# CR6.net
KiCad netlist of a schematic drawn in EAGLE
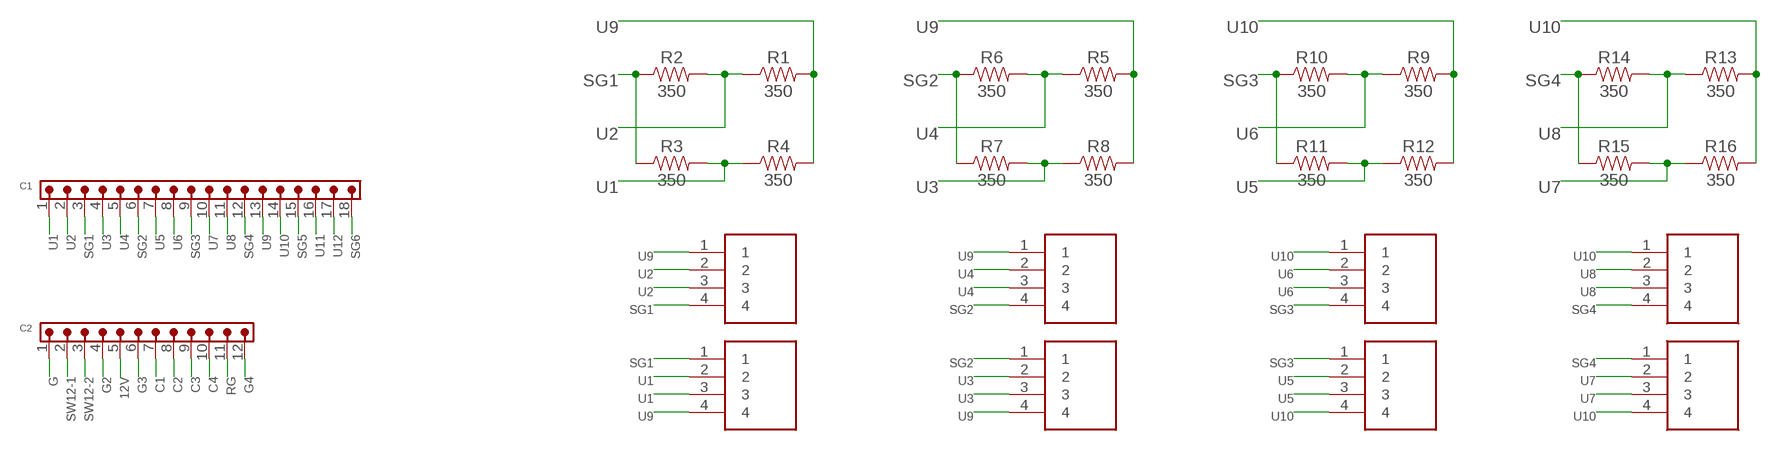
[diagram p0: schematic, sheet 1]

(export (version "E")
  (design (tool "Eeschema 10.0.6"))
  (components
    (comp (ref "C1")
      (value "WURTH_CONNECTORS_WR-TBL-PLUGGABLE-CONNECTOR_691311500018")
      (footprint "eagle-import:WURTH_CONNECTORS_WR-TBL-PLUGGABLE-CONNECTOR_691311500018")
      (libsource (lib "eagle-import") (part "WURTH_CONNECTORS_WR-TBL-PLUGGABLE-CONNECTOR_691311500018"))
    )
    (comp (ref "C2")
      (value "WURTH_CONNECTORS_WR-TBL-PLUGGABLE-CONNECTOR_691311500012")
      (footprint "eagle-import:WURTH_CONNECTORS_WR-TBL-PLUGGABLE-CONNECTOR_691311500012")
      (libsource (lib "eagle-import") (part "WURTH_CONNECTORS_WR-TBL-PLUGGABLE-CONNECTOR_691311500012"))
    )
    (comp (ref "J1")
      (value "1725672")
      (footprint "eagle-import:1725672-4-2.54")
      (fields (field (name "RS_PART_NUMBER") "3924476"))
      (libsource (lib "eagle-import") (part "1725672"))
    )
    (comp (ref "J2")
      (value "1725672")
      (footprint "eagle-import:1725672-4-2.54")
      (fields (field (name "RS_PART_NUMBER") "3924476"))
      (libsource (lib "eagle-import") (part "1725672"))
    )
    (comp (ref "J5")
      (value "1725672")
      (footprint "eagle-import:1725672-4-2.54")
      (fields (field (name "RS_PART_NUMBER") "3924476"))
      (libsource (lib "eagle-import") (part "1725672"))
    )
    (comp (ref "J6")
      (value "1725672")
      (footprint "eagle-import:1725672-4-2.54")
      (fields (field (name "RS_PART_NUMBER") "3924476"))
      (libsource (lib "eagle-import") (part "1725672"))
    )
    (comp (ref "J9")
      (value "1725672")
      (footprint "eagle-import:1725672-4-2.54")
      (fields (field (name "RS_PART_NUMBER") "3924476"))
      (libsource (lib "eagle-import") (part "1725672"))
    )
    (comp (ref "J10")
      (value "1725672")
      (footprint "eagle-import:1725672-4-2.54")
      (fields (field (name "RS_PART_NUMBER") "3924476"))
      (libsource (lib "eagle-import") (part "1725672"))
    )
    (comp (ref "J13")
      (value "1725672")
      (footprint "eagle-import:1725672-4-2.54")
      (fields (field (name "RS_PART_NUMBER") "3924476"))
      (libsource (lib "eagle-import") (part "1725672"))
    )
    (comp (ref "J14")
      (value "1725672")
      (footprint "eagle-import:1725672-4-2.54")
      (fields (field (name "RS_PART_NUMBER") "3924476"))
      (libsource (lib "eagle-import") (part "1725672"))
    )
    (comp (ref "R1")
      (value "350")
      (footprint "eagle-import:AXIAL-0.3")
      (libsource (lib "eagle-import") (part "330OHM-HORIZ-1/10W-5%"))
    )
    (comp (ref "R2")
      (value "350")
      (footprint "eagle-import:AXIAL-0.3")
      (libsource (lib "eagle-import") (part "330OHM-HORIZ-1/10W-5%"))
    )
    (comp (ref "R3")
      (value "350")
      (footprint "eagle-import:AXIAL-0.3")
      (libsource (lib "eagle-import") (part "330OHM-HORIZ-1/10W-5%"))
    )
    (comp (ref "R4")
      (value "350")
      (footprint "eagle-import:AXIAL-0.3")
      (libsource (lib "eagle-import") (part "330OHM-HORIZ-1/10W-5%"))
    )
    (comp (ref "R5")
      (value "350")
      (footprint "eagle-import:AXIAL-0.3")
      (libsource (lib "eagle-import") (part "330OHM-HORIZ-1/10W-5%"))
    )
    (comp (ref "R6")
      (value "350")
      (footprint "eagle-import:AXIAL-0.3")
      (libsource (lib "eagle-import") (part "330OHM-HORIZ-1/10W-5%"))
    )
    (comp (ref "R7")
      (value "350")
      (footprint "eagle-import:AXIAL-0.3")
      (libsource (lib "eagle-import") (part "330OHM-HORIZ-1/10W-5%"))
    )
    (comp (ref "R8")
      (value "350")
      (footprint "eagle-import:AXIAL-0.3")
      (libsource (lib "eagle-import") (part "330OHM-HORIZ-1/10W-5%"))
    )
    (comp (ref "R9")
      (value "350")
      (footprint "eagle-import:AXIAL-0.3")
      (libsource (lib "eagle-import") (part "330OHM-HORIZ-1/10W-5%"))
    )
    (comp (ref "R10")
      (value "350")
      (footprint "eagle-import:AXIAL-0.3")
      (libsource (lib "eagle-import") (part "330OHM-HORIZ-1/10W-5%"))
    )
    (comp (ref "R11")
      (value "350")
      (footprint "eagle-import:AXIAL-0.3")
      (libsource (lib "eagle-import") (part "330OHM-HORIZ-1/10W-5%"))
    )
    (comp (ref "R12")
      (value "350")
      (footprint "eagle-import:AXIAL-0.3")
      (libsource (lib "eagle-import") (part "330OHM-HORIZ-1/10W-5%"))
    )
    (comp (ref "R13")
      (value "350")
      (footprint "eagle-import:AXIAL-0.3")
      (libsource (lib "eagle-import") (part "330OHM-HORIZ-1/10W-5%"))
    )
    (comp (ref "R14")
      (value "350")
      (footprint "eagle-import:AXIAL-0.3")
      (libsource (lib "eagle-import") (part "330OHM-HORIZ-1/10W-5%"))
    )
    (comp (ref "R15")
      (value "350")
      (footprint "eagle-import:AXIAL-0.3")
      (libsource (lib "eagle-import") (part "330OHM-HORIZ-1/10W-5%"))
    )
    (comp (ref "R16")
      (value "350")
      (footprint "eagle-import:AXIAL-0.3")
      (libsource (lib "eagle-import") (part "330OHM-HORIZ-1/10W-5%"))
    )
  )
  (nets
    (net (code "1") (name "12V") (class "Default")
      (node (ref "C2") (pin "5") (pinfunction "5_5") (pintype "passive"))
    )
    (net (code "2") (name "C1") (class "Default")
      (node (ref "C2") (pin "7") (pinfunction "7_7") (pintype "passive"))
    )
    (net (code "3") (name "C2") (class "Default")
      (node (ref "C2") (pin "8") (pinfunction "8_8") (pintype "passive"))
    )
    (net (code "4") (name "C3") (class "Default")
      (node (ref "C2") (pin "9") (pinfunction "9_9") (pintype "passive"))
    )
    (net (code "5") (name "C4") (class "Default")
      (node (ref "C2") (pin "10") (pinfunction "10_10") (pintype "passive"))
    )
    (net (code "6") (name "G") (class "Default")
      (node (ref "C2") (pin "1") (pinfunction "1_1") (pintype "passive"))
    )
    (net (code "7") (name "G2") (class "Default")
      (node (ref "C2") (pin "4") (pinfunction "4_4") (pintype "passive"))
    )
    (net (code "8") (name "G3") (class "Default")
      (node (ref "C2") (pin "6") (pinfunction "6_6") (pintype "passive"))
    )
    (net (code "9") (name "G4") (class "Default")
      (node (ref "C2") (pin "12") (pinfunction "12_12") (pintype "passive"))
    )
    (net (code "10") (name "RG") (class "Default")
      (node (ref "C2") (pin "11") (pinfunction "11_11") (pintype "passive"))
    )
    (net (code "11") (name "SG1") (class "Default")
      (node (ref "C1") (pin "3") (pinfunction "3_3") (pintype "passive"))
      (node (ref "J1") (pin "4") (pinfunction "4_4") (pintype "bidirectional"))
      (node (ref "J2") (pin "1") (pinfunction "1_1") (pintype "bidirectional"))
      (node (ref "R2") (pin "P$1") (pinfunction "1_P$1") (pintype "passive"))
      (node (ref "R3") (pin "P$1") (pinfunction "1_P$1") (pintype "passive"))
    )
    (net (code "12") (name "SG2") (class "Default")
      (node (ref "C1") (pin "6") (pinfunction "6_6") (pintype "passive"))
      (node (ref "J5") (pin "4") (pinfunction "4_4") (pintype "bidirectional"))
      (node (ref "J6") (pin "1") (pinfunction "1_1") (pintype "bidirectional"))
      (node (ref "R6") (pin "P$1") (pinfunction "1_P$1") (pintype "passive"))
      (node (ref "R7") (pin "P$1") (pinfunction "1_P$1") (pintype "passive"))
    )
    (net (code "13") (name "SG3") (class "Default")
      (node (ref "C1") (pin "9") (pinfunction "9_9") (pintype "passive"))
      (node (ref "J10") (pin "1") (pinfunction "1_1") (pintype "bidirectional"))
      (node (ref "J9") (pin "4") (pinfunction "4_4") (pintype "bidirectional"))
      (node (ref "R10") (pin "P$1") (pinfunction "1_P$1") (pintype "passive"))
      (node (ref "R11") (pin "P$1") (pinfunction "1_P$1") (pintype "passive"))
    )
    (net (code "14") (name "SG4") (class "Default")
      (node (ref "C1") (pin "12") (pinfunction "12_12") (pintype "passive"))
      (node (ref "J13") (pin "4") (pinfunction "4_4") (pintype "bidirectional"))
      (node (ref "J14") (pin "1") (pinfunction "1_1") (pintype "bidirectional"))
      (node (ref "R14") (pin "P$1") (pinfunction "1_P$1") (pintype "passive"))
      (node (ref "R15") (pin "P$1") (pinfunction "1_P$1") (pintype "passive"))
    )
    (net (code "15") (name "SG5") (class "Default")
      (node (ref "C1") (pin "15") (pinfunction "15_15") (pintype "passive"))
    )
    (net (code "16") (name "SG6") (class "Default")
      (node (ref "C1") (pin "18") (pinfunction "18_18") (pintype "passive"))
    )
    (net (code "17") (name "SW12-1") (class "Default")
      (node (ref "C2") (pin "2") (pinfunction "2_2") (pintype "passive"))
    )
    (net (code "18") (name "SW12-2") (class "Default")
      (node (ref "C2") (pin "3") (pinfunction "3_3") (pintype "passive"))
    )
    (net (code "19") (name "U1") (class "Default")
      (node (ref "C1") (pin "1") (pinfunction "1_1") (pintype "passive"))
      (node (ref "J2") (pin "2") (pinfunction "2_2") (pintype "bidirectional"))
      (node (ref "J2") (pin "3") (pinfunction "3_3") (pintype "bidirectional"))
      (node (ref "R3") (pin "P$2") (pinfunction "2_P$2") (pintype "passive"))
      (node (ref "R4") (pin "P$1") (pinfunction "1_P$1") (pintype "passive"))
    )
    (net (code "20") (name "U2") (class "Default")
      (node (ref "C1") (pin "2") (pinfunction "2_2") (pintype "passive"))
      (node (ref "J1") (pin "2") (pinfunction "2_2") (pintype "bidirectional"))
      (node (ref "J1") (pin "3") (pinfunction "3_3") (pintype "bidirectional"))
      (node (ref "R1") (pin "P$1") (pinfunction "1_P$1") (pintype "passive"))
      (node (ref "R2") (pin "P$2") (pinfunction "2_P$2") (pintype "passive"))
    )
    (net (code "21") (name "U3") (class "Default")
      (node (ref "C1") (pin "4") (pinfunction "4_4") (pintype "passive"))
      (node (ref "J6") (pin "2") (pinfunction "2_2") (pintype "bidirectional"))
      (node (ref "J6") (pin "3") (pinfunction "3_3") (pintype "bidirectional"))
      (node (ref "R7") (pin "P$2") (pinfunction "2_P$2") (pintype "passive"))
      (node (ref "R8") (pin "P$1") (pinfunction "1_P$1") (pintype "passive"))
    )
    (net (code "22") (name "U4") (class "Default")
      (node (ref "C1") (pin "5") (pinfunction "5_5") (pintype "passive"))
      (node (ref "J5") (pin "2") (pinfunction "2_2") (pintype "bidirectional"))
      (node (ref "J5") (pin "3") (pinfunction "3_3") (pintype "bidirectional"))
      (node (ref "R5") (pin "P$1") (pinfunction "1_P$1") (pintype "passive"))
      (node (ref "R6") (pin "P$2") (pinfunction "2_P$2") (pintype "passive"))
    )
    (net (code "23") (name "U5") (class "Default")
      (node (ref "C1") (pin "7") (pinfunction "7_7") (pintype "passive"))
      (node (ref "J10") (pin "2") (pinfunction "2_2") (pintype "bidirectional"))
      (node (ref "J10") (pin "3") (pinfunction "3_3") (pintype "bidirectional"))
      (node (ref "R11") (pin "P$2") (pinfunction "2_P$2") (pintype "passive"))
      (node (ref "R12") (pin "P$1") (pinfunction "1_P$1") (pintype "passive"))
    )
    (net (code "24") (name "U6") (class "Default")
      (node (ref "C1") (pin "8") (pinfunction "8_8") (pintype "passive"))
      (node (ref "J9") (pin "2") (pinfunction "2_2") (pintype "bidirectional"))
      (node (ref "J9") (pin "3") (pinfunction "3_3") (pintype "bidirectional"))
      (node (ref "R10") (pin "P$2") (pinfunction "2_P$2") (pintype "passive"))
      (node (ref "R9") (pin "P$1") (pinfunction "1_P$1") (pintype "passive"))
    )
    (net (code "25") (name "U7") (class "Default")
      (node (ref "C1") (pin "10") (pinfunction "10_10") (pintype "passive"))
      (node (ref "J14") (pin "2") (pinfunction "2_2") (pintype "bidirectional"))
      (node (ref "J14") (pin "3") (pinfunction "3_3") (pintype "bidirectional"))
      (node (ref "R15") (pin "P$2") (pinfunction "2_P$2") (pintype "passive"))
      (node (ref "R16") (pin "P$1") (pinfunction "1_P$1") (pintype "passive"))
    )
    (net (code "26") (name "U8") (class "Default")
      (node (ref "C1") (pin "11") (pinfunction "11_11") (pintype "passive"))
      (node (ref "J13") (pin "2") (pinfunction "2_2") (pintype "bidirectional"))
      (node (ref "J13") (pin "3") (pinfunction "3_3") (pintype "bidirectional"))
      (node (ref "R13") (pin "P$1") (pinfunction "1_P$1") (pintype "passive"))
      (node (ref "R14") (pin "P$2") (pinfunction "2_P$2") (pintype "passive"))
    )
    (net (code "27") (name "U9") (class "Default")
      (node (ref "C1") (pin "13") (pinfunction "13_13") (pintype "passive"))
      (node (ref "J1") (pin "1") (pinfunction "1_1") (pintype "bidirectional"))
      (node (ref "J2") (pin "4") (pinfunction "4_4") (pintype "bidirectional"))
      (node (ref "J5") (pin "1") (pinfunction "1_1") (pintype "bidirectional"))
      (node (ref "J6") (pin "4") (pinfunction "4_4") (pintype "bidirectional"))
      (node (ref "R1") (pin "P$2") (pinfunction "2_P$2") (pintype "passive"))
      (node (ref "R4") (pin "P$2") (pinfunction "2_P$2") (pintype "passive"))
      (node (ref "R5") (pin "P$2") (pinfunction "2_P$2") (pintype "passive"))
      (node (ref "R8") (pin "P$2") (pinfunction "2_P$2") (pintype "passive"))
    )
    (net (code "28") (name "U10") (class "Default")
      (node (ref "C1") (pin "14") (pinfunction "14_14") (pintype "passive"))
      (node (ref "J10") (pin "4") (pinfunction "4_4") (pintype "bidirectional"))
      (node (ref "J13") (pin "1") (pinfunction "1_1") (pintype "bidirectional"))
      (node (ref "J14") (pin "4") (pinfunction "4_4") (pintype "bidirectional"))
      (node (ref "J9") (pin "1") (pinfunction "1_1") (pintype "bidirectional"))
      (node (ref "R12") (pin "P$2") (pinfunction "2_P$2") (pintype "passive"))
      (node (ref "R13") (pin "P$2") (pinfunction "2_P$2") (pintype "passive"))
      (node (ref "R16") (pin "P$2") (pinfunction "2_P$2") (pintype "passive"))
      (node (ref "R9") (pin "P$2") (pinfunction "2_P$2") (pintype "passive"))
    )
    (net (code "29") (name "U11") (class "Default")
      (node (ref "C1") (pin "16") (pinfunction "16_16") (pintype "passive"))
    )
    (net (code "30") (name "U12") (class "Default")
      (node (ref "C1") (pin "17") (pinfunction "17_17") (pintype "passive"))
    )
  )
)
